# SCH_555-Timer_2025-10-19.net
KiCad netlist of a schematic drawn in EasyEDA
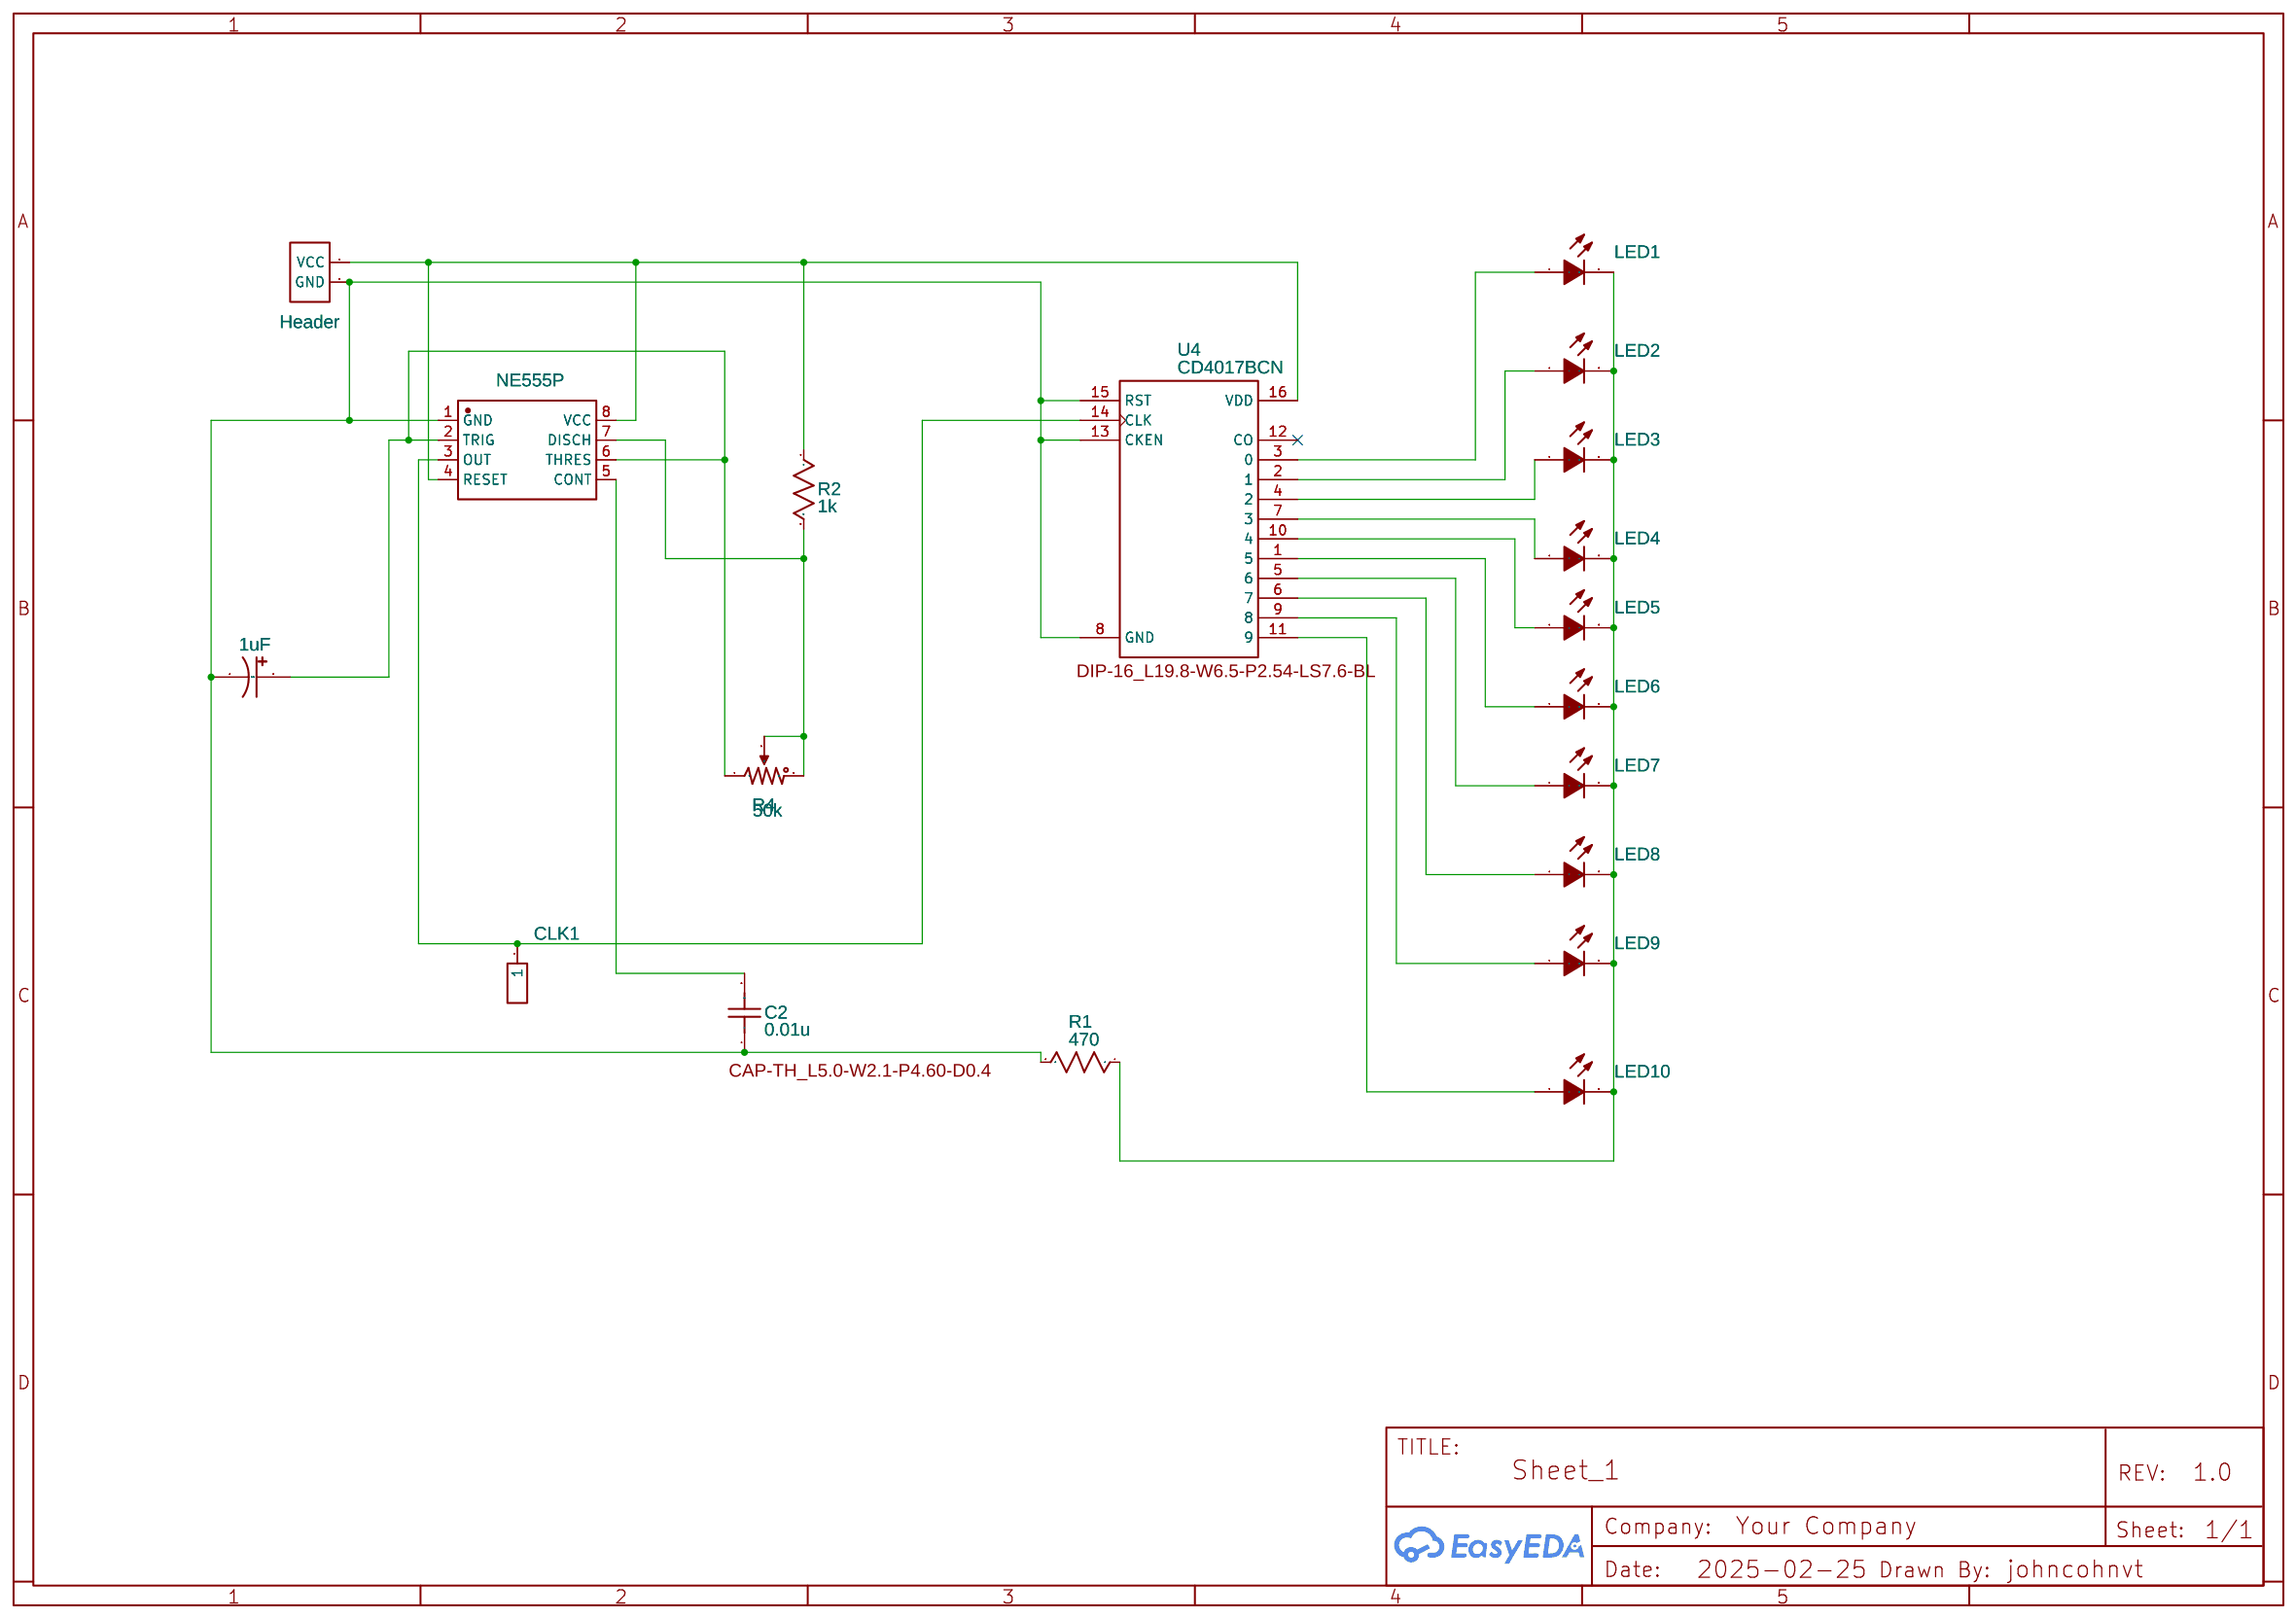
[diagram p0: schematic sheet]

(export (version "E")
  (design (tool "Eeschema 10.0.6"))
  (components
    (comp (ref "C1")
      (value "1uF")
      (fields (field (name "Manufacturer Part") "UVZ1H010MDD") (field (name "Manufacturer") "Nichicon(尼吉康)"))
      (libsource (lib "") (part "UVZ1H010MDD"))
    )
    (comp (ref "C2") (value "0.01u") (libsource (lib "") (part "C_0603_US")))
    (comp (ref "CLK1")
      (value "C81276")
      (fields
        (field (name "Manufacturer Part") "2.54-1*1P针")
        (field (name "Manufacturer") "BOOMELE(Boom Precision Elec)")
      )
      (libsource (lib "") (part "Header-Male-2.54_1x1"))
    )
    (comp (ref "H1") (value "Header") (libsource (lib "") (part "HEADER-FEMALE-2.54_1X2")))
    (comp (ref "LED1") (value "LED_5MM") (libsource (lib "") (part "LED_5MM")))
    (comp (ref "LED2") (value "LED_5MM") (libsource (lib "") (part "LED_5MM")))
    (comp (ref "LED3") (value "LED_5MM") (libsource (lib "") (part "LED_5MM")))
    (comp (ref "LED4") (value "LED_5MM") (libsource (lib "") (part "LED_5MM")))
    (comp (ref "LED5") (value "LED_5MM") (libsource (lib "") (part "LED_5MM")))
    (comp (ref "LED6") (value "LED_5MM") (libsource (lib "") (part "LED_5MM")))
    (comp (ref "LED7") (value "LED_5MM") (libsource (lib "") (part "LED_5MM")))
    (comp (ref "LED8") (value "LED_5MM") (libsource (lib "") (part "LED_5MM")))
    (comp (ref "LED9") (value "LED_5MM") (libsource (lib "") (part "LED_5MM")))
    (comp (ref "LED10") (value "LED_5MM") (libsource (lib "") (part "LED_5MM")))
    (comp (ref "R1")
      (value "470")
      (fields (field (name "Manufacturer Part") "?"))
      (libsource (lib "") (part "Resistor_1"))
    )
    (comp (ref "R2")
      (value "1k")
      (fields (field (name "Manufacturer Part") "?"))
      (libsource (lib "") (part "Resistor"))
    )
    (comp (ref "R4")
      (value "50k")
      (fields (field (name "Manufacturer Part") "?"))
      (libsource (lib "") (part "Potentiometer"))
    )
    (comp (ref "U2")
      (value "NE555P")
      (fields (field (name "Manufacturer") "TI(德州仪器)"))
      (libsource (lib "") (part "NE555P"))
    )
    (comp (ref "U4") (value "CD4017BCN") (libsource (lib "") (part "CD4017BCN")))
  )
  (nets
    (net (code "1") (name "Net-(H1-GND)") (class "Default")
      (node (ref "C1") (pin "2") (pinfunction "2_2") (pintype "unspecified"))
      (node (ref "C2") (pin "1") (pinfunction "1_1") (pintype "unspecified"))
      (node (ref "H1") (pin "2") (pinfunction "GND_2") (pintype "unspecified"))
      (node (ref "R1") (pin "2") (pinfunction "2_2") (pintype "unspecified"))
      (node (ref "U2") (pin "1") (pinfunction "GND_1") (pintype "unspecified"))
      (node (ref "U4") (pin "13") (pinfunction "CKEN_13") (pintype "unspecified"))
      (node (ref "U4") (pin "15") (pinfunction "RST_15") (pintype "unspecified"))
      (node (ref "U4") (pin "8") (pinfunction "GND_8") (pintype "passive"))
    )
    (net (code "2") (name "Net-(H1-VCC)") (class "Default")
      (node (ref "H1") (pin "1") (pinfunction "VCC_1") (pintype "unspecified"))
      (node (ref "R2") (pin "1") (pinfunction "1_1") (pintype "unspecified"))
      (node (ref "U2") (pin "4") (pinfunction "RESET_4") (pintype "unspecified"))
      (node (ref "U2") (pin "8") (pinfunction "VCC_8") (pintype "unspecified"))
      (node (ref "U4") (pin "16") (pinfunction "VDD_16") (pintype "passive"))
    )
    (net (code "3") (name "Net-(LED1-A)") (class "Default")
      (node (ref "LED1") (pin "1") (pinfunction "A_1") (pintype "input"))
      (node (ref "U4") (pin "3") (pinfunction "0_3") (pintype "output"))
    )
    (net (code "4") (name "Net-(LED1-K)") (class "Default")
      (node (ref "LED1") (pin "2") (pinfunction "K_2") (pintype "input"))
      (node (ref "LED10") (pin "2") (pinfunction "K_2") (pintype "input"))
      (node (ref "LED2") (pin "2") (pinfunction "K_2") (pintype "input"))
      (node (ref "LED3") (pin "2") (pinfunction "K_2") (pintype "input"))
      (node (ref "LED4") (pin "2") (pinfunction "K_2") (pintype "input"))
      (node (ref "LED5") (pin "2") (pinfunction "K_2") (pintype "input"))
      (node (ref "LED6") (pin "2") (pinfunction "K_2") (pintype "input"))
      (node (ref "LED7") (pin "2") (pinfunction "K_2") (pintype "input"))
      (node (ref "LED8") (pin "2") (pinfunction "K_2") (pintype "input"))
      (node (ref "LED9") (pin "2") (pinfunction "K_2") (pintype "input"))
      (node (ref "R1") (pin "1") (pinfunction "1_1") (pintype "unspecified"))
    )
    (net (code "5") (name "Net-(LED2-A)") (class "Default")
      (node (ref "LED2") (pin "1") (pinfunction "A_1") (pintype "input"))
      (node (ref "U4") (pin "2") (pinfunction "1_2") (pintype "output"))
    )
    (net (code "6") (name "Net-(LED3-A)") (class "Default")
      (node (ref "LED3") (pin "1") (pinfunction "A_1") (pintype "input"))
      (node (ref "U4") (pin "4") (pinfunction "2_4") (pintype "output"))
    )
    (net (code "7") (name "Net-(LED4-A)") (class "Default")
      (node (ref "LED4") (pin "1") (pinfunction "A_1") (pintype "input"))
      (node (ref "U4") (pin "7") (pinfunction "3_7") (pintype "output"))
    )
    (net (code "8") (name "Net-(LED5-A)") (class "Default")
      (node (ref "LED5") (pin "1") (pinfunction "A_1") (pintype "input"))
      (node (ref "U4") (pin "10") (pinfunction "4_10") (pintype "output"))
    )
    (net (code "9") (name "Net-(LED6-A)") (class "Default")
      (node (ref "LED6") (pin "1") (pinfunction "A_1") (pintype "input"))
      (node (ref "U4") (pin "1") (pinfunction "5_1") (pintype "output"))
    )
    (net (code "10") (name "Net-(LED7-A)") (class "Default")
      (node (ref "LED7") (pin "1") (pinfunction "A_1") (pintype "input"))
      (node (ref "U4") (pin "5") (pinfunction "6_5") (pintype "output"))
    )
    (net (code "11") (name "Net-(LED8-A)") (class "Default")
      (node (ref "LED8") (pin "1") (pinfunction "A_1") (pintype "input"))
      (node (ref "U4") (pin "6") (pinfunction "7_6") (pintype "output"))
    )
    (net (code "12") (name "Net-(LED9-A)") (class "Default")
      (node (ref "LED9") (pin "1") (pinfunction "A_1") (pintype "input"))
      (node (ref "U4") (pin "9") (pinfunction "8_9") (pintype "output"))
    )
    (net (code "13") (name "Net-(LED10-A)") (class "Default")
      (node (ref "LED10") (pin "1") (pinfunction "A_1") (pintype "input"))
      (node (ref "U4") (pin "11") (pinfunction "9_11") (pintype "output"))
    )
    (net (code "14") (name "Net-(R4-2)") (class "Default")
      (node (ref "R2") (pin "2") (pinfunction "2_2") (pintype "unspecified"))
      (node (ref "R4") (pin "2") (pinfunction "3_2") (pintype "unspecified"))
      (node (ref "R4") (pin "3") (pinfunction "2_3") (pintype "unspecified"))
      (node (ref "U2") (pin "7") (pinfunction "DISCH_7") (pintype "unspecified"))
    )
    (net (code "15") (name "Net-(U2-CONT)") (class "Default")
      (node (ref "C2") (pin "2") (pinfunction "2_2") (pintype "unspecified"))
      (node (ref "U2") (pin "5") (pinfunction "CONT_5") (pintype "unspecified"))
    )
    (net (code "16") (name "Net-(U2-OUT)") (class "Default")
      (node (ref "CLK1") (pin "1") (pinfunction "1_1") (pintype "unspecified"))
      (node (ref "U2") (pin "3") (pinfunction "OUT_3") (pintype "unspecified"))
      (node (ref "U4") (pin "14") (pinfunction "CLK_14") (pintype "unspecified"))
    )
    (net (code "17") (name "Net-(U2-THRES)") (class "Default")
      (node (ref "C1") (pin "1") (pinfunction "1_1") (pintype "unspecified"))
      (node (ref "R4") (pin "1") (pinfunction "1_1") (pintype "unspecified"))
      (node (ref "U2") (pin "2") (pinfunction "TRIG_2") (pintype "unspecified"))
      (node (ref "U2") (pin "6") (pinfunction "THRES_6") (pintype "unspecified"))
    )
    (net (code "18") (name "unconnected-(U4-CO-Pad12)") (class "Default")
      (node (ref "U4") (pin "12") (pinfunction "CO_12") (pintype "output+no_connect"))
    )
  )
)
